# 12LED.net
KiCad netlist of a schematic drawn in Altium Designer
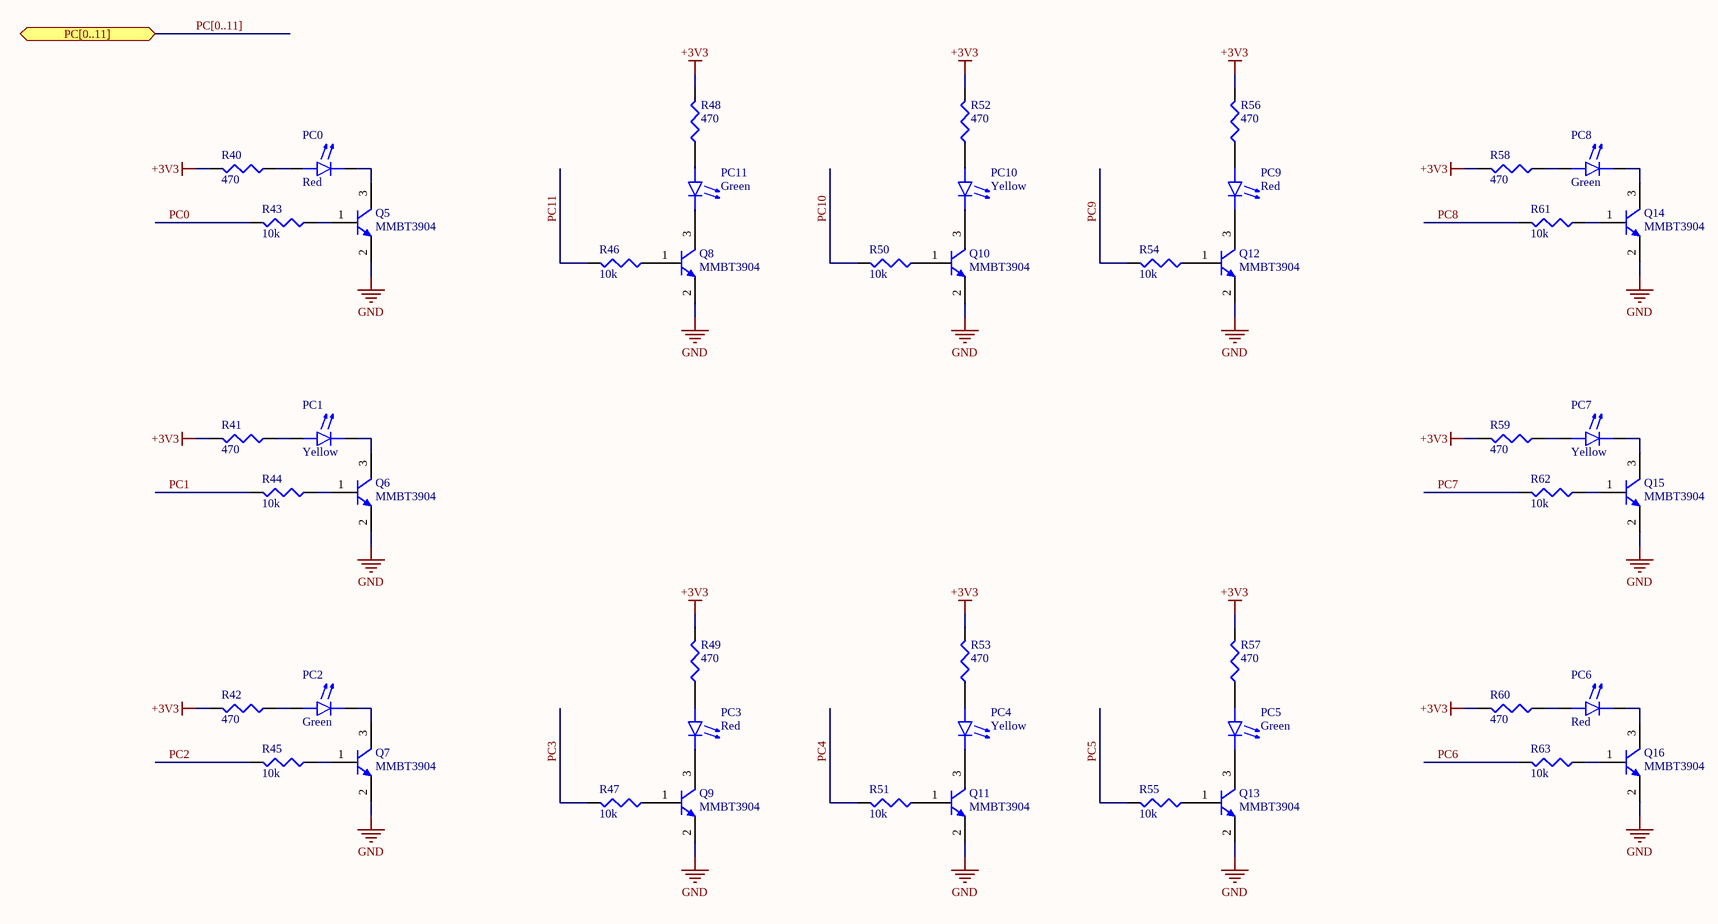
[diagram p0: 12LED.SchDoc]

(export (version "E")
  (design (tool "Eeschema 10.0.6"))
  (components
    (comp (ref "PC0")
      (value "Red")
      (footprint "0805 (2012 Metric) Red")
      (description "Oreki")
      (fields (field (name "JLCPCB PART #") "C142306"))
      (libsource (lib "Ho Chi Minh City University of Technology") (part "Symbol"))
    )
    (comp (ref "PC1")
      (value "Yellow")
      (footprint "0805 (2012 Metric) Yellow")
      (description "Oreki")
      (fields (field (name "JLCPCB PART #") "C2296"))
      (libsource (lib "Ho Chi Minh City University of Technology") (part "Symbol"))
    )
    (comp (ref "PC2")
      (value "Green")
      (footprint "0805 (2012 Metric) Green")
      (description "Oreki")
      (fields (field (name "JLCPCB PART #") "C389524"))
      (libsource (lib "Ho Chi Minh City University of Technology") (part "Symbol"))
    )
    (comp (ref "PC3")
      (value "Red")
      (footprint "0805 (2012 Metric) Red")
      (description "Oreki")
      (fields (field (name "JLCPCB PART #") "C142306"))
      (libsource (lib "Ho Chi Minh City University of Technology") (part "Symbol"))
    )
    (comp (ref "PC4")
      (value "Yellow")
      (footprint "0805 (2012 Metric) Yellow")
      (description "Oreki")
      (fields (field (name "JLCPCB PART #") "C2296"))
      (libsource (lib "Ho Chi Minh City University of Technology") (part "Symbol"))
    )
    (comp (ref "PC5")
      (value "Green")
      (footprint "0805 (2012 Metric) Green")
      (description "Oreki")
      (fields (field (name "JLCPCB PART #") "C389524"))
      (libsource (lib "Ho Chi Minh City University of Technology") (part "Symbol"))
    )
    (comp (ref "PC6")
      (value "Red")
      (footprint "0805 (2012 Metric) Red")
      (description "Oreki")
      (fields (field (name "JLCPCB PART #") "C142306"))
      (libsource (lib "Ho Chi Minh City University of Technology") (part "Symbol"))
    )
    (comp (ref "PC7")
      (value "Yellow")
      (footprint "0805 (2012 Metric) Yellow")
      (description "Oreki")
      (fields (field (name "JLCPCB PART #") "C2296"))
      (libsource (lib "Ho Chi Minh City University of Technology") (part "Symbol"))
    )
    (comp (ref "PC8")
      (value "Green")
      (footprint "0805 (2012 Metric) Green")
      (description "Oreki")
      (fields (field (name "JLCPCB PART #") "C389524"))
      (libsource (lib "Ho Chi Minh City University of Technology") (part "Symbol"))
    )
    (comp (ref "PC9")
      (value "Red")
      (footprint "0805 (2012 Metric) Red")
      (description "Oreki")
      (fields (field (name "JLCPCB PART #") "C142306"))
      (libsource (lib "Ho Chi Minh City University of Technology") (part "Symbol"))
    )
    (comp (ref "PC10")
      (value "Yellow")
      (footprint "0805 (2012 Metric) Yellow")
      (description "Oreki")
      (fields (field (name "JLCPCB PART #") "C2296"))
      (libsource (lib "Ho Chi Minh City University of Technology") (part "Symbol"))
    )
    (comp (ref "PC11")
      (value "Green")
      (footprint "0805 (2012 Metric) Green")
      (description "Oreki")
      (fields (field (name "JLCPCB PART #") "C389524"))
      (libsource (lib "Ho Chi Minh City University of Technology") (part "Symbol"))
    )
    (comp (ref "Q5")
      (value "MMBT3904")
      (footprint "FAIR-SOT23-3_V")
      (description "NPN General Purpose Amplifier, 40 V, 0.2 A, -55 to 150 degC, 3-Pin SOT23, RoHS, Tape and Reel")
      (fields (field (name "JLCPCB PART #") "C20526") (field (name "MANUFACTURER") "Fairchild Semiconductor"))
      (libsource (lib "Ho Chi Minh City University of Technology") (part "BJT-NPN-BEC-3"))
    )
    (comp (ref "Q6")
      (value "MMBT3904")
      (footprint "FAIR-SOT23-3_V")
      (description "NPN General Purpose Amplifier, 40 V, 0.2 A, -55 to 150 degC, 3-Pin SOT23, RoHS, Tape and Reel")
      (fields (field (name "JLCPCB PART #") "C20526") (field (name "MANUFACTURER") "Fairchild Semiconductor"))
      (libsource (lib "Ho Chi Minh City University of Technology") (part "BJT-NPN-BEC-3"))
    )
    (comp (ref "Q7")
      (value "MMBT3904")
      (footprint "FAIR-SOT23-3_V")
      (description "NPN General Purpose Amplifier, 40 V, 0.2 A, -55 to 150 degC, 3-Pin SOT23, RoHS, Tape and Reel")
      (fields (field (name "JLCPCB PART #") "C20526") (field (name "MANUFACTURER") "Fairchild Semiconductor"))
      (libsource (lib "Ho Chi Minh City University of Technology") (part "BJT-NPN-BEC-3"))
    )
    (comp (ref "Q8")
      (value "MMBT3904")
      (footprint "FAIR-SOT23-3_V")
      (description "NPN General Purpose Amplifier, 40 V, 0.2 A, -55 to 150 degC, 3-Pin SOT23, RoHS, Tape and Reel")
      (fields (field (name "JLCPCB PART #") "C20526") (field (name "MANUFACTURER") "Fairchild Semiconductor"))
      (libsource (lib "Ho Chi Minh City University of Technology") (part "BJT-NPN-BEC-3"))
    )
    (comp (ref "Q9")
      (value "MMBT3904")
      (footprint "FAIR-SOT23-3_V")
      (description "NPN General Purpose Amplifier, 40 V, 0.2 A, -55 to 150 degC, 3-Pin SOT23, RoHS, Tape and Reel")
      (fields (field (name "JLCPCB PART #") "C20526") (field (name "MANUFACTURER") "Fairchild Semiconductor"))
      (libsource (lib "Ho Chi Minh City University of Technology") (part "BJT-NPN-BEC-3"))
    )
    (comp (ref "Q10")
      (value "MMBT3904")
      (footprint "FAIR-SOT23-3_V")
      (description "NPN General Purpose Amplifier, 40 V, 0.2 A, -55 to 150 degC, 3-Pin SOT23, RoHS, Tape and Reel")
      (fields (field (name "JLCPCB PART #") "C20526") (field (name "MANUFACTURER") "Fairchild Semiconductor"))
      (libsource (lib "Ho Chi Minh City University of Technology") (part "BJT-NPN-BEC-3"))
    )
    (comp (ref "Q11")
      (value "MMBT3904")
      (footprint "FAIR-SOT23-3_V")
      (description "NPN General Purpose Amplifier, 40 V, 0.2 A, -55 to 150 degC, 3-Pin SOT23, RoHS, Tape and Reel")
      (fields (field (name "JLCPCB PART #") "C20526") (field (name "MANUFACTURER") "Fairchild Semiconductor"))
      (libsource (lib "Ho Chi Minh City University of Technology") (part "BJT-NPN-BEC-3"))
    )
    (comp (ref "Q12")
      (value "MMBT3904")
      (footprint "FAIR-SOT23-3_V")
      (description "NPN General Purpose Amplifier, 40 V, 0.2 A, -55 to 150 degC, 3-Pin SOT23, RoHS, Tape and Reel")
      (fields (field (name "JLCPCB PART #") "C20526") (field (name "MANUFACTURER") "Fairchild Semiconductor"))
      (libsource (lib "Ho Chi Minh City University of Technology") (part "BJT-NPN-BEC-3"))
    )
    (comp (ref "Q13")
      (value "MMBT3904")
      (footprint "FAIR-SOT23-3_V")
      (description "NPN General Purpose Amplifier, 40 V, 0.2 A, -55 to 150 degC, 3-Pin SOT23, RoHS, Tape and Reel")
      (fields (field (name "JLCPCB PART #") "C20526") (field (name "MANUFACTURER") "Fairchild Semiconductor"))
      (libsource (lib "Ho Chi Minh City University of Technology") (part "BJT-NPN-BEC-3"))
    )
    (comp (ref "Q14")
      (value "MMBT3904")
      (footprint "FAIR-SOT23-3_V")
      (description "NPN General Purpose Amplifier, 40 V, 0.2 A, -55 to 150 degC, 3-Pin SOT23, RoHS, Tape and Reel")
      (fields (field (name "JLCPCB PART #") "C20526") (field (name "MANUFACTURER") "Fairchild Semiconductor"))
      (libsource (lib "Ho Chi Minh City University of Technology") (part "BJT-NPN-BEC-3"))
    )
    (comp (ref "Q15")
      (value "MMBT3904")
      (footprint "FAIR-SOT23-3_V")
      (description "NPN General Purpose Amplifier, 40 V, 0.2 A, -55 to 150 degC, 3-Pin SOT23, RoHS, Tape and Reel")
      (fields (field (name "JLCPCB PART #") "C20526") (field (name "MANUFACTURER") "Fairchild Semiconductor"))
      (libsource (lib "Ho Chi Minh City University of Technology") (part "BJT-NPN-BEC-3"))
    )
    (comp (ref "Q16")
      (value "MMBT3904")
      (footprint "FAIR-SOT23-3_V")
      (description "NPN General Purpose Amplifier, 40 V, 0.2 A, -55 to 150 degC, 3-Pin SOT23, RoHS, Tape and Reel")
      (fields (field (name "JLCPCB PART #") "C20526") (field (name "MANUFACTURER") "Fairchild Semiconductor"))
      (libsource (lib "Ho Chi Minh City University of Technology") (part "BJT-NPN-BEC-3"))
    )
    (comp (ref "R40")
      (value "470")
      (footprint "0805 (2012 Metric)")
      (description "Oreki")
      (fields (field (name "Comment") "220"))
      (libsource (lib "Ho Chi Minh City University of Technology") (part "RES-2"))
    )
    (comp (ref "R41")
      (value "470")
      (footprint "0805 (2012 Metric)")
      (description "Oreki")
      (fields (field (name "Comment") "220"))
      (libsource (lib "Ho Chi Minh City University of Technology") (part "RES-2"))
    )
    (comp (ref "R42")
      (value "470")
      (footprint "0805 (2012 Metric)")
      (description "Oreki")
      (fields (field (name "Comment") "220"))
      (libsource (lib "Ho Chi Minh City University of Technology") (part "RES-2"))
    )
    (comp (ref "R43")
      (value "10k")
      (footprint "0805 (2012 Metric)")
      (description "Oreki")
      (fields (field (name "Comment") "3k3"))
      (libsource (lib "Ho Chi Minh City University of Technology") (part "RES-2"))
    )
    (comp (ref "R44")
      (value "10k")
      (footprint "0805 (2012 Metric)")
      (description "Oreki")
      (fields (field (name "Comment") "3k3"))
      (libsource (lib "Ho Chi Minh City University of Technology") (part "RES-2"))
    )
    (comp (ref "R45")
      (value "10k")
      (footprint "0805 (2012 Metric)")
      (description "Oreki")
      (fields (field (name "Comment") "3k3"))
      (libsource (lib "Ho Chi Minh City University of Technology") (part "RES-2"))
    )
    (comp (ref "R46")
      (value "10k")
      (footprint "0805 (2012 Metric)")
      (description "Oreki")
      (fields (field (name "Comment") "3k3"))
      (libsource (lib "Ho Chi Minh City University of Technology") (part "RES-2"))
    )
    (comp (ref "R47")
      (value "10k")
      (footprint "0805 (2012 Metric)")
      (description "Oreki")
      (fields (field (name "Comment") "3k3"))
      (libsource (lib "Ho Chi Minh City University of Technology") (part "RES-2"))
    )
    (comp (ref "R48")
      (value "470")
      (footprint "0805 (2012 Metric)")
      (description "Oreki")
      (fields (field (name "Comment") "220"))
      (libsource (lib "Ho Chi Minh City University of Technology") (part "RES-2"))
    )
    (comp (ref "R49")
      (value "470")
      (footprint "0805 (2012 Metric)")
      (description "Oreki")
      (fields (field (name "Comment") "220"))
      (libsource (lib "Ho Chi Minh City University of Technology") (part "RES-2"))
    )
    (comp (ref "R50")
      (value "10k")
      (footprint "0805 (2012 Metric)")
      (description "Oreki")
      (fields (field (name "Comment") "3k3"))
      (libsource (lib "Ho Chi Minh City University of Technology") (part "RES-2"))
    )
    (comp (ref "R51")
      (value "10k")
      (footprint "0805 (2012 Metric)")
      (description "Oreki")
      (fields (field (name "Comment") "3k3"))
      (libsource (lib "Ho Chi Minh City University of Technology") (part "RES-2"))
    )
    (comp (ref "R52")
      (value "470")
      (footprint "0805 (2012 Metric)")
      (description "Oreki")
      (fields (field (name "Comment") "220"))
      (libsource (lib "Ho Chi Minh City University of Technology") (part "RES-2"))
    )
    (comp (ref "R53")
      (value "470")
      (footprint "0805 (2012 Metric)")
      (description "Oreki")
      (fields (field (name "Comment") "220"))
      (libsource (lib "Ho Chi Minh City University of Technology") (part "RES-2"))
    )
    (comp (ref "R54")
      (value "10k")
      (footprint "0805 (2012 Metric)")
      (description "Oreki")
      (fields (field (name "Comment") "3k3"))
      (libsource (lib "Ho Chi Minh City University of Technology") (part "RES-2"))
    )
    (comp (ref "R55")
      (value "10k")
      (footprint "0805 (2012 Metric)")
      (description "Oreki")
      (fields (field (name "Comment") "3k3"))
      (libsource (lib "Ho Chi Minh City University of Technology") (part "RES-2"))
    )
    (comp (ref "R56")
      (value "470")
      (footprint "0805 (2012 Metric)")
      (description "Oreki")
      (fields (field (name "Comment") "220"))
      (libsource (lib "Ho Chi Minh City University of Technology") (part "RES-2"))
    )
    (comp (ref "R57")
      (value "470")
      (footprint "0805 (2012 Metric)")
      (description "Oreki")
      (fields (field (name "Comment") "220"))
      (libsource (lib "Ho Chi Minh City University of Technology") (part "RES-2"))
    )
    (comp (ref "R58")
      (value "470")
      (footprint "0805 (2012 Metric)")
      (description "Oreki")
      (fields (field (name "Comment") "220"))
      (libsource (lib "Ho Chi Minh City University of Technology") (part "RES-2"))
    )
    (comp (ref "R59")
      (value "470")
      (footprint "0805 (2012 Metric)")
      (description "Oreki")
      (fields (field (name "Comment") "220"))
      (libsource (lib "Ho Chi Minh City University of Technology") (part "RES-2"))
    )
    (comp (ref "R60")
      (value "470")
      (footprint "0805 (2012 Metric)")
      (description "Oreki")
      (fields (field (name "Comment") "220"))
      (libsource (lib "Ho Chi Minh City University of Technology") (part "RES-2"))
    )
    (comp (ref "R61")
      (value "10k")
      (footprint "0805 (2012 Metric)")
      (description "Oreki")
      (fields (field (name "Comment") "3k3"))
      (libsource (lib "Ho Chi Minh City University of Technology") (part "RES-2"))
    )
    (comp (ref "R62")
      (value "10k")
      (footprint "0805 (2012 Metric)")
      (description "Oreki")
      (fields (field (name "Comment") "3k3"))
      (libsource (lib "Ho Chi Minh City University of Technology") (part "RES-2"))
    )
    (comp (ref "R63")
      (value "10k")
      (footprint "0805 (2012 Metric)")
      (description "Oreki")
      (fields (field (name "Comment") "3k3"))
      (libsource (lib "Ho Chi Minh City University of Technology") (part "RES-2"))
    )
  )
  (nets
    (net (code "1") (name "+3V3") (class "Default")
      (node (ref "R40") (pin "2") (pinfunction "2_2") (pintype "passive"))
      (node (ref "R41") (pin "2") (pinfunction "2_2") (pintype "passive"))
      (node (ref "R42") (pin "2") (pinfunction "2_2") (pintype "passive"))
      (node (ref "R48") (pin "2") (pinfunction "2_2") (pintype "passive"))
      (node (ref "R49") (pin "2") (pinfunction "2_2") (pintype "passive"))
      (node (ref "R52") (pin "2") (pinfunction "2_2") (pintype "passive"))
      (node (ref "R53") (pin "2") (pinfunction "2_2") (pintype "passive"))
      (node (ref "R56") (pin "2") (pinfunction "2_2") (pintype "passive"))
      (node (ref "R57") (pin "2") (pinfunction "2_2") (pintype "passive"))
      (node (ref "R58") (pin "2") (pinfunction "2_2") (pintype "passive"))
      (node (ref "R59") (pin "2") (pinfunction "2_2") (pintype "passive"))
      (node (ref "R60") (pin "2") (pinfunction "2_2") (pintype "passive"))
    )
    (net (code "2") (name "/PC0") (class "Default")
      (node (ref "R43") (pin "2") (pinfunction "2_2") (pintype "passive"))
    )
    (net (code "3") (name "/PC1") (class "Default")
      (node (ref "R44") (pin "2") (pinfunction "2_2") (pintype "passive"))
    )
    (net (code "4") (name "/PC2") (class "Default")
      (node (ref "R45") (pin "2") (pinfunction "2_2") (pintype "passive"))
    )
    (net (code "5") (name "/PC3") (class "Default")
      (node (ref "R47") (pin "2") (pinfunction "2_2") (pintype "passive"))
    )
    (net (code "6") (name "/PC4") (class "Default")
      (node (ref "R51") (pin "2") (pinfunction "2_2") (pintype "passive"))
    )
    (net (code "7") (name "/PC5") (class "Default")
      (node (ref "R55") (pin "2") (pinfunction "2_2") (pintype "passive"))
    )
    (net (code "8") (name "/PC6") (class "Default")
      (node (ref "R63") (pin "2") (pinfunction "2_2") (pintype "passive"))
    )
    (net (code "9") (name "/PC7") (class "Default")
      (node (ref "R62") (pin "2") (pinfunction "2_2") (pintype "passive"))
    )
    (net (code "10") (name "/PC8") (class "Default")
      (node (ref "R61") (pin "2") (pinfunction "2_2") (pintype "passive"))
    )
    (net (code "11") (name "/PC9") (class "Default")
      (node (ref "R54") (pin "2") (pinfunction "2_2") (pintype "passive"))
    )
    (net (code "12") (name "/PC10") (class "Default")
      (node (ref "R50") (pin "2") (pinfunction "2_2") (pintype "passive"))
    )
    (net (code "13") (name "/PC11") (class "Default")
      (node (ref "R46") (pin "2") (pinfunction "2_2") (pintype "passive"))
    )
    (net (code "15") (name "GND") (class "Default")
      (node (ref "Q10") (pin "2") (pinfunction "E_2") (pintype "passive"))
      (node (ref "Q11") (pin "2") (pinfunction "E_2") (pintype "passive"))
      (node (ref "Q12") (pin "2") (pinfunction "E_2") (pintype "passive"))
      (node (ref "Q13") (pin "2") (pinfunction "E_2") (pintype "passive"))
      (node (ref "Q14") (pin "2") (pinfunction "E_2") (pintype "passive"))
      (node (ref "Q15") (pin "2") (pinfunction "E_2") (pintype "passive"))
      (node (ref "Q16") (pin "2") (pinfunction "E_2") (pintype "passive"))
      (node (ref "Q5") (pin "2") (pinfunction "E_2") (pintype "passive"))
      (node (ref "Q6") (pin "2") (pinfunction "E_2") (pintype "passive"))
      (node (ref "Q7") (pin "2") (pinfunction "E_2") (pintype "passive"))
      (node (ref "Q8") (pin "2") (pinfunction "E_2") (pintype "passive"))
      (node (ref "Q9") (pin "2") (pinfunction "E_2") (pintype "passive"))
    )
    (net (code "16") (name "Net-(PC0-A)") (class "Default")
      (node (ref "PC0") (pin "2") (pinfunction "A_2") (pintype "passive"))
      (node (ref "R40") (pin "1") (pinfunction "1_1") (pintype "passive"))
    )
    (net (code "17") (name "Net-(PC0-K)") (class "Default")
      (node (ref "PC0") (pin "1") (pinfunction "K_1") (pintype "passive"))
      (node (ref "Q5") (pin "3") (pinfunction "C_3") (pintype "passive"))
    )
    (net (code "18") (name "Net-(PC1-A)") (class "Default")
      (node (ref "PC1") (pin "2") (pinfunction "A_2") (pintype "passive"))
      (node (ref "R41") (pin "1") (pinfunction "1_1") (pintype "passive"))
    )
    (net (code "19") (name "Net-(PC1-K)") (class "Default")
      (node (ref "PC1") (pin "1") (pinfunction "K_1") (pintype "passive"))
      (node (ref "Q6") (pin "3") (pinfunction "C_3") (pintype "passive"))
    )
    (net (code "20") (name "Net-(PC2-A)") (class "Default")
      (node (ref "PC2") (pin "2") (pinfunction "A_2") (pintype "passive"))
      (node (ref "R42") (pin "1") (pinfunction "1_1") (pintype "passive"))
    )
    (net (code "21") (name "Net-(PC2-K)") (class "Default")
      (node (ref "PC2") (pin "1") (pinfunction "K_1") (pintype "passive"))
      (node (ref "Q7") (pin "3") (pinfunction "C_3") (pintype "passive"))
    )
    (net (code "22") (name "Net-(PC3-A)") (class "Default")
      (node (ref "PC3") (pin "2") (pinfunction "A_2") (pintype "passive"))
      (node (ref "R49") (pin "1") (pinfunction "1_1") (pintype "passive"))
    )
    (net (code "23") (name "Net-(PC3-K)") (class "Default")
      (node (ref "PC3") (pin "1") (pinfunction "K_1") (pintype "passive"))
      (node (ref "Q9") (pin "3") (pinfunction "C_3") (pintype "passive"))
    )
    (net (code "24") (name "Net-(PC4-A)") (class "Default")
      (node (ref "PC4") (pin "2") (pinfunction "A_2") (pintype "passive"))
      (node (ref "R53") (pin "1") (pinfunction "1_1") (pintype "passive"))
    )
    (net (code "25") (name "Net-(PC4-K)") (class "Default")
      (node (ref "PC4") (pin "1") (pinfunction "K_1") (pintype "passive"))
      (node (ref "Q11") (pin "3") (pinfunction "C_3") (pintype "passive"))
    )
    (net (code "26") (name "Net-(PC5-A)") (class "Default")
      (node (ref "PC5") (pin "2") (pinfunction "A_2") (pintype "passive"))
      (node (ref "R57") (pin "1") (pinfunction "1_1") (pintype "passive"))
    )
    (net (code "27") (name "Net-(PC5-K)") (class "Default")
      (node (ref "PC5") (pin "1") (pinfunction "K_1") (pintype "passive"))
      (node (ref "Q13") (pin "3") (pinfunction "C_3") (pintype "passive"))
    )
    (net (code "28") (name "Net-(PC6-A)") (class "Default")
      (node (ref "PC6") (pin "2") (pinfunction "A_2") (pintype "passive"))
      (node (ref "R60") (pin "1") (pinfunction "1_1") (pintype "passive"))
    )
    (net (code "29") (name "Net-(PC6-K)") (class "Default")
      (node (ref "PC6") (pin "1") (pinfunction "K_1") (pintype "passive"))
      (node (ref "Q16") (pin "3") (pinfunction "C_3") (pintype "passive"))
    )
    (net (code "30") (name "Net-(PC7-A)") (class "Default")
      (node (ref "PC7") (pin "2") (pinfunction "A_2") (pintype "passive"))
      (node (ref "R59") (pin "1") (pinfunction "1_1") (pintype "passive"))
    )
    (net (code "31") (name "Net-(PC7-K)") (class "Default")
      (node (ref "PC7") (pin "1") (pinfunction "K_1") (pintype "passive"))
      (node (ref "Q15") (pin "3") (pinfunction "C_3") (pintype "passive"))
    )
    (net (code "32") (name "Net-(PC8-A)") (class "Default")
      (node (ref "PC8") (pin "2") (pinfunction "A_2") (pintype "passive"))
      (node (ref "R58") (pin "1") (pinfunction "1_1") (pintype "passive"))
    )
    (net (code "33") (name "Net-(PC8-K)") (class "Default")
      (node (ref "PC8") (pin "1") (pinfunction "K_1") (pintype "passive"))
      (node (ref "Q14") (pin "3") (pinfunction "C_3") (pintype "passive"))
    )
    (net (code "34") (name "Net-(PC9-A)") (class "Default")
      (node (ref "PC9") (pin "2") (pinfunction "A_2") (pintype "passive"))
      (node (ref "R56") (pin "1") (pinfunction "1_1") (pintype "passive"))
    )
    (net (code "35") (name "Net-(PC9-K)") (class "Default")
      (node (ref "PC9") (pin "1") (pinfunction "K_1") (pintype "passive"))
      (node (ref "Q12") (pin "3") (pinfunction "C_3") (pintype "passive"))
    )
    (net (code "36") (name "Net-(PC10-A)") (class "Default")
      (node (ref "PC10") (pin "2") (pinfunction "A_2") (pintype "passive"))
      (node (ref "R52") (pin "1") (pinfunction "1_1") (pintype "passive"))
    )
    (net (code "37") (name "Net-(PC10-K)") (class "Default")
      (node (ref "PC10") (pin "1") (pinfunction "K_1") (pintype "passive"))
      (node (ref "Q10") (pin "3") (pinfunction "C_3") (pintype "passive"))
    )
    (net (code "38") (name "Net-(PC11-A)") (class "Default")
      (node (ref "PC11") (pin "2") (pinfunction "A_2") (pintype "passive"))
      (node (ref "R48") (pin "1") (pinfunction "1_1") (pintype "passive"))
    )
    (net (code "39") (name "Net-(PC11-K)") (class "Default")
      (node (ref "PC11") (pin "1") (pinfunction "K_1") (pintype "passive"))
      (node (ref "Q8") (pin "3") (pinfunction "C_3") (pintype "passive"))
    )
    (net (code "40") (name "Net-(Q5-B)") (class "Default")
      (node (ref "Q5") (pin "1") (pinfunction "B_1") (pintype "passive"))
      (node (ref "R43") (pin "1") (pinfunction "1_1") (pintype "passive"))
    )
    (net (code "41") (name "Net-(Q6-B)") (class "Default")
      (node (ref "Q6") (pin "1") (pinfunction "B_1") (pintype "passive"))
      (node (ref "R44") (pin "1") (pinfunction "1_1") (pintype "passive"))
    )
    (net (code "42") (name "Net-(Q7-B)") (class "Default")
      (node (ref "Q7") (pin "1") (pinfunction "B_1") (pintype "passive"))
      (node (ref "R45") (pin "1") (pinfunction "1_1") (pintype "passive"))
    )
    (net (code "43") (name "Net-(Q8-B)") (class "Default")
      (node (ref "Q8") (pin "1") (pinfunction "B_1") (pintype "passive"))
      (node (ref "R46") (pin "1") (pinfunction "1_1") (pintype "passive"))
    )
    (net (code "44") (name "Net-(Q9-B)") (class "Default")
      (node (ref "Q9") (pin "1") (pinfunction "B_1") (pintype "passive"))
      (node (ref "R47") (pin "1") (pinfunction "1_1") (pintype "passive"))
    )
    (net (code "45") (name "Net-(Q10-B)") (class "Default")
      (node (ref "Q10") (pin "1") (pinfunction "B_1") (pintype "passive"))
      (node (ref "R50") (pin "1") (pinfunction "1_1") (pintype "passive"))
    )
    (net (code "46") (name "Net-(Q11-B)") (class "Default")
      (node (ref "Q11") (pin "1") (pinfunction "B_1") (pintype "passive"))
      (node (ref "R51") (pin "1") (pinfunction "1_1") (pintype "passive"))
    )
    (net (code "47") (name "Net-(Q12-B)") (class "Default")
      (node (ref "Q12") (pin "1") (pinfunction "B_1") (pintype "passive"))
      (node (ref "R54") (pin "1") (pinfunction "1_1") (pintype "passive"))
    )
    (net (code "48") (name "Net-(Q13-B)") (class "Default")
      (node (ref "Q13") (pin "1") (pinfunction "B_1") (pintype "passive"))
      (node (ref "R55") (pin "1") (pinfunction "1_1") (pintype "passive"))
    )
    (net (code "49") (name "Net-(Q14-B)") (class "Default")
      (node (ref "Q14") (pin "1") (pinfunction "B_1") (pintype "passive"))
      (node (ref "R61") (pin "1") (pinfunction "1_1") (pintype "passive"))
    )
    (net (code "50") (name "Net-(Q15-B)") (class "Default")
      (node (ref "Q15") (pin "1") (pinfunction "B_1") (pintype "passive"))
      (node (ref "R62") (pin "1") (pinfunction "1_1") (pintype "passive"))
    )
    (net (code "51") (name "Net-(Q16-B)") (class "Default")
      (node (ref "Q16") (pin "1") (pinfunction "B_1") (pintype "passive"))
      (node (ref "R63") (pin "1") (pinfunction "1_1") (pintype "passive"))
    )
  )
)
